# STM.net
KiCad netlist of a schematic drawn in Altium Designer
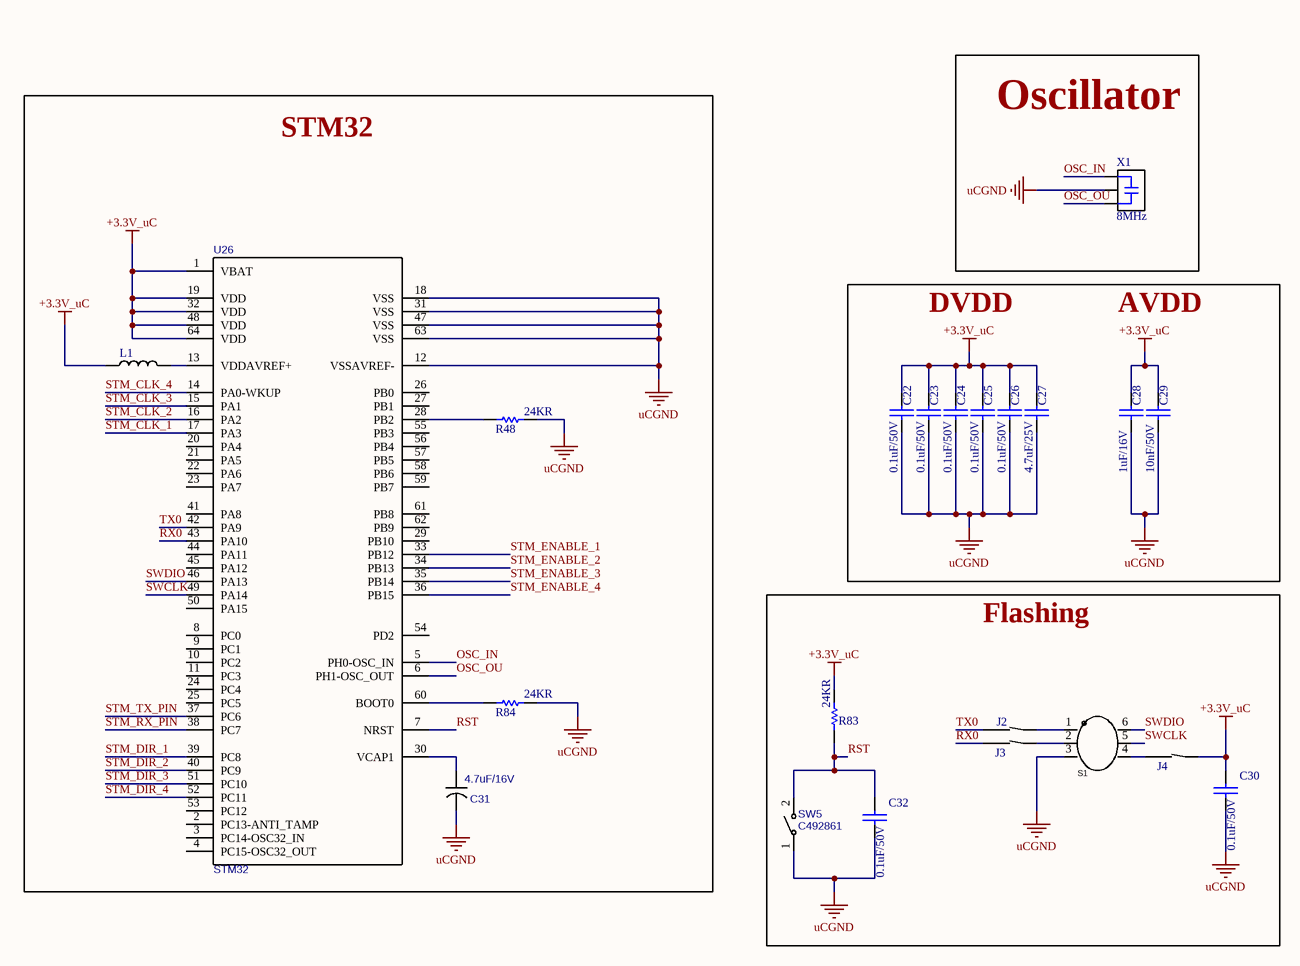
[diagram p0: STM.SchDoc]

(export (version "E")
  (design (tool "Eeschema 10.0.6"))
  (components
    (comp (ref "C22")
      (value "0.1uF/50V")
      (footprint "PCBComponent_1")
      (description "C1591")
      (fields (field (name "CREATED BY") "NourAldin"))
      (libsource (lib "0603 Capacitor") (part "0603 Capacitor"))
    )
    (comp (ref "C23")
      (value "0.1uF/50V")
      (footprint "PCBComponent_1")
      (description "C1591")
      (fields (field (name "CREATED BY") "NourAldin"))
      (libsource (lib "0603 Capacitor") (part "0603 Capacitor"))
    )
    (comp (ref "C24")
      (value "0.1uF/50V")
      (footprint "PCBComponent_1")
      (description "C1591")
      (fields (field (name "CREATED BY") "NourAldin"))
      (libsource (lib "0603 Capacitor") (part "0603 Capacitor"))
    )
    (comp (ref "C25")
      (value "0.1uF/50V")
      (footprint "PCBComponent_1")
      (description "C1591")
      (fields (field (name "CREATED BY") "NourAldin"))
      (libsource (lib "0603 Capacitor") (part "0603 Capacitor"))
    )
    (comp (ref "C26")
      (value "0.1uF/50V")
      (footprint "PCBComponent_1")
      (description "C1591")
      (fields (field (name "CREATED BY") "NourAldin"))
      (libsource (lib "0603 Capacitor") (part "0603 Capacitor"))
    )
    (comp (ref "C27")
      (value "4.7uF/25V")
      (footprint "PCBComponent_1")
      (description "C69335")
      (fields (field (name "CREATED BY") "NourAldin"))
      (libsource (lib "0603 Capacitor") (part "0603 Capacitor"))
    )
    (comp (ref "C28")
      (value "1uF/16V")
      (footprint "PCBComponent_1")
      (description "C1592")
      (fields (field (name "CREATED BY") "NourAldin"))
      (libsource (lib "0603 Capacitor") (part "0603 Capacitor"))
    )
    (comp (ref "C29")
      (value "10nF/50V")
      (footprint "PCBComponent_1")
      (description "C100042")
      (fields (field (name "CREATED BY") "NourAldin"))
      (libsource (lib "0603 Capacitor") (part "0603 Capacitor"))
    )
    (comp (ref "C30")
      (value "0.1uF/50V")
      (footprint "PCBComponent_1")
      (description "C1591")
      (fields (field (name "CREATED BY") "NourAldin"))
      (libsource (lib "0603 Capacitor") (part "0603 Capacitor"))
    )
    (comp (ref "C31")
      (value "4.7uF/16V")
      (footprint "CASE-B_3528")
      (description "C7206")
      (fields
        (field (name "MANUFACTURER") "Kyocera AVX")
        (field (name "MANUFACTURER PART") "TAJR106K006RNJ")
        (field (name "CONTRIBUTOR") "LCSC")
      )
      (libsource (lib "DIVERSE") (part "3528  Tantalum Cap"))
    )
    (comp (ref "C32")
      (value "0.1uF/50V")
      (footprint "PCBComponent_1")
      (description "C1591")
      (fields (field (name "CREATED BY") "NourAldin"))
      (libsource (lib "0603 Capacitor") (part "0603 Capacitor"))
    )
    (comp (ref "J2") (value "Jumper") (footprint "Jumper") (libsource (lib "DIVERSE") (part "Jumper")))
    (comp (ref "J3") (value "Jumper") (footprint "Jumper") (libsource (lib "DIVERSE") (part "Jumper")))
    (comp (ref "J4") (value "Jumper") (footprint "Jumper") (libsource (lib "DIVERSE") (part "Jumper")))
    (comp (ref "L1")
      (value "CMI201209X100KT")
      (footprint "INDC2012X06N")
      (description "C99366")
      (fields (field (name "CREATED BY") "NourAldin"))
      (libsource (lib "0805 Inductor") (part "0805 SMD INDUCTOR"))
    )
    (comp (ref "R48")
      (value "24KR")
      (footprint "RESC1608X06N")
      (description "C2930081")
      (fields (field (name "CREATED BY") "NourAldin"))
      (libsource (lib "0603 Resistor") (part "0603 Resistor"))
    )
    (comp (ref "R83")
      (value "24KR")
      (footprint "RESC1608X06N")
      (description "C2930081")
      (fields (field (name "CREATED BY") "NourAldin"))
      (libsource (lib "0603 Resistor") (part "0603 Resistor"))
    )
    (comp (ref "R84")
      (value "24KR")
      (footprint "RESC1608X06N")
      (description "C2930081")
      (fields (field (name "CREATED BY") "NourAldin"))
      (libsource (lib "0603 Resistor") (part "0603 Resistor"))
    )
    (comp (ref "S1")
      (value "STM Debug")
      (footprint "STM_Debug")
      (description "Wurth Elektronik 490107670612")
      (fields
        (field (name "MANUFACTURER") "XKB Connection(中国星坤)")
        (field (name "MANUFACTURER PART") "X4621WVS-2x03I-C40D64")
      )
      (libsource (lib "DIVERSE") (part "STM Debug"))
    )
    (comp (ref "SW5")
      (value "C492861")
      (footprint "SW-SMD_L4.0-W3.0-LS4.8")
      (fields
        (field (name "MANUFACTURER") "Yuandi(元迪)")
        (field (name "MANUFACTURER PART") "TS-1071AS-A1B3-D4")
        (field (name "CONTRIBUTOR") "LCSC")
      )
      (libsource (lib "DIVERSE") (part "tact switch"))
    )
    (comp (ref "U26")
      (value "STM32")
      (footprint "LQFP-64_L10.0-W10.0-P0.50-LS12.0-BL")
      (description "C74524")
      (fields (field (name "MANUFACTURER") "ST(意法半导体)") (field (name "MANUFACTURER PART") "STM32F401RCT6"))
      (libsource (lib "DIVERSE") (part "STM32F401RCT6"))
    )
    (comp (ref "X1")
      (value "8MHz")
      (footprint "SMD3213-3P")
      (description "C907975")
      (fields
        (field (name "MANUFACTURER") "Murata")
        (field (name "MANUFACTURER PART NUMBER") "CSTCE16M0V53-R0")
      )
      (libsource (lib "CO2_Lib") (part "CSTCE16M0V53-R0"))
    )
  )
  (nets
    (net (code "1") (name "+3.3V_uC") (class "Default")
      (node (ref "C22") (pin "2") (pinfunction "2_2") (pintype "passive"))
      (node (ref "C23") (pin "2") (pinfunction "2_2") (pintype "passive"))
      (node (ref "C24") (pin "2") (pinfunction "2_2") (pintype "passive"))
      (node (ref "C25") (pin "2") (pinfunction "2_2") (pintype "passive"))
      (node (ref "C26") (pin "2") (pinfunction "2_2") (pintype "passive"))
      (node (ref "C27") (pin "2") (pinfunction "2_2") (pintype "passive"))
      (node (ref "C28") (pin "2") (pinfunction "2_2") (pintype "passive"))
      (node (ref "C29") (pin "2") (pinfunction "2_2") (pintype "passive"))
      (node (ref "C30") (pin "2") (pinfunction "2_2") (pintype "passive"))
      (node (ref "J4") (pin "2") (pinfunction "2_2") (pintype "passive"))
      (node (ref "L1") (pin "1") (pinfunction "1_1") (pintype "passive"))
      (node (ref "R83") (pin "1") (pinfunction "1_1") (pintype "passive"))
      (node (ref "U26") (pin "1") (pinfunction "VBAT_1") (pintype "passive"))
      (node (ref "U26") (pin "19") (pinfunction "VDD_19") (pintype "passive"))
      (node (ref "U26") (pin "32") (pinfunction "VDD_32") (pintype "passive"))
      (node (ref "U26") (pin "48") (pinfunction "VDD_48") (pintype "passive"))
      (node (ref "U26") (pin "64") (pinfunction "VDD_64") (pintype "passive"))
    )
    (net (code "2") (name "/OSC_IN") (class "Default")
      (node (ref "U26") (pin "5") (pinfunction "PH0-OSC_IN_5") (pintype "passive"))
      (node (ref "X1") (pin "1") (pinfunction "1_1") (pintype "passive"))
    )
    (net (code "3") (name "/OSC_OU") (class "Default")
      (node (ref "U26") (pin "6") (pinfunction "PH1-OSC_OUT_6") (pintype "passive"))
      (node (ref "X1") (pin "3") (pinfunction "3_3") (pintype "passive"))
    )
    (net (code "4") (name "/RST") (class "Default")
      (node (ref "C32") (pin "2") (pinfunction "2_2") (pintype "passive"))
      (node (ref "R83") (pin "2") (pinfunction "2_2") (pintype "passive"))
      (node (ref "SW5") (pin "2") (pinfunction "2_2") (pintype "passive"))
      (node (ref "U26") (pin "7") (pinfunction "NRST_7") (pintype "passive"))
    )
    (net (code "5") (name "/RX0") (class "Default")
      (node (ref "J3") (pin "1") (pinfunction "1_1") (pintype "passive"))
      (node (ref "U26") (pin "43") (pinfunction "PA10_43") (pintype "passive"))
    )
    (net (code "6") (name "/STM_CLK_1") (class "Default")
      (node (ref "U26") (pin "17") (pinfunction "PA3_17") (pintype "passive"))
    )
    (net (code "7") (name "/STM_CLK_2") (class "Default")
      (node (ref "U26") (pin "16") (pinfunction "PA2_16") (pintype "passive"))
    )
    (net (code "8") (name "/STM_CLK_3") (class "Default")
      (node (ref "U26") (pin "15") (pinfunction "PA1_15") (pintype "passive"))
    )
    (net (code "9") (name "/STM_CLK_4") (class "Default")
      (node (ref "U26") (pin "14") (pinfunction "PA0-WKUP_14") (pintype "passive"))
    )
    (net (code "10") (name "/STM_DIR_1") (class "Default")
      (node (ref "U26") (pin "39") (pinfunction "PC8_39") (pintype "passive"))
    )
    (net (code "11") (name "/STM_DIR_2") (class "Default")
      (node (ref "U26") (pin "40") (pinfunction "PC9_40") (pintype "passive"))
    )
    (net (code "12") (name "/STM_DIR_3") (class "Default")
      (node (ref "U26") (pin "51") (pinfunction "PC10_51") (pintype "passive"))
    )
    (net (code "13") (name "/STM_DIR_4") (class "Default")
      (node (ref "U26") (pin "52") (pinfunction "PC11_52") (pintype "passive"))
    )
    (net (code "14") (name "/STM_ENABLE_1") (class "Default")
      (node (ref "U26") (pin "33") (pinfunction "PB12_33") (pintype "passive"))
    )
    (net (code "15") (name "/STM_ENABLE_2") (class "Default")
      (node (ref "U26") (pin "34") (pinfunction "PB13_34") (pintype "passive"))
    )
    (net (code "16") (name "/STM_ENABLE_3") (class "Default")
      (node (ref "U26") (pin "35") (pinfunction "PB14_35") (pintype "passive"))
    )
    (net (code "17") (name "/STM_ENABLE_4") (class "Default")
      (node (ref "U26") (pin "36") (pinfunction "PB15_36") (pintype "passive"))
    )
    (net (code "18") (name "/STM_RX_PIN") (class "Default")
      (node (ref "U26") (pin "38") (pinfunction "PC7_38") (pintype "passive"))
    )
    (net (code "19") (name "/STM_TX_PIN") (class "Default")
      (node (ref "U26") (pin "37") (pinfunction "PC6_37") (pintype "passive"))
    )
    (net (code "20") (name "/SWCLK") (class "Default")
      (node (ref "S1") (pin "5") (pinfunction "5_5") (pintype "passive"))
      (node (ref "U26") (pin "49") (pinfunction "PA14_49") (pintype "passive"))
    )
    (net (code "21") (name "/SWDIO") (class "Default")
      (node (ref "S1") (pin "6") (pinfunction "6_6") (pintype "passive"))
      (node (ref "U26") (pin "46") (pinfunction "PA13_46") (pintype "passive"))
    )
    (net (code "22") (name "/TX0") (class "Default")
      (node (ref "J2") (pin "1") (pinfunction "1_1") (pintype "passive"))
      (node (ref "U26") (pin "42") (pinfunction "PA9_42") (pintype "passive"))
    )
    (net (code "23") (name "Net-(J2-Pad2)") (class "Default")
      (node (ref "J2") (pin "2") (pinfunction "2_2") (pintype "passive"))
      (node (ref "S1") (pin "1") (pinfunction "1_1") (pintype "passive"))
    )
    (net (code "24") (name "Net-(J3-Pad2)") (class "Default")
      (node (ref "J3") (pin "2") (pinfunction "2_2") (pintype "passive"))
      (node (ref "S1") (pin "2") (pinfunction "2_2") (pintype "passive"))
    )
    (net (code "25") (name "Net-(J4-Pad1)") (class "Default")
      (node (ref "J4") (pin "1") (pinfunction "1_1") (pintype "passive"))
      (node (ref "S1") (pin "4") (pinfunction "4_4") (pintype "passive"))
    )
    (net (code "26") (name "Net-(U26-BOOT0)") (class "Default")
      (node (ref "R84") (pin "2") (pinfunction "2_2") (pintype "passive"))
      (node (ref "U26") (pin "60") (pinfunction "BOOT0_60") (pintype "passive"))
    )
    (net (code "27") (name "Net-(U26-PB2)") (class "Default")
      (node (ref "R48") (pin "2") (pinfunction "2_2") (pintype "passive"))
      (node (ref "U26") (pin "28") (pinfunction "PB2_28") (pintype "passive"))
    )
    (net (code "28") (name "Net-(U26-VCAP1)") (class "Default")
      (node (ref "C31") (pin "1") (pinfunction "1_1") (pintype "passive"))
      (node (ref "U26") (pin "30") (pinfunction "VCAP1_30") (pintype "passive"))
    )
    (net (code "29") (name "Net-(U26-VDDAVREF+)") (class "Default")
      (node (ref "L1") (pin "2") (pinfunction "2_2") (pintype "passive"))
      (node (ref "U26") (pin "13") (pinfunction "VDDAVREF+_13") (pintype "passive"))
    )
    (net (code "30") (name "uCGND") (class "Default")
      (node (ref "C22") (pin "1") (pinfunction "1_1") (pintype "passive"))
      (node (ref "C23") (pin "1") (pinfunction "1_1") (pintype "passive"))
      (node (ref "C24") (pin "1") (pinfunction "1_1") (pintype "passive"))
      (node (ref "C25") (pin "1") (pinfunction "1_1") (pintype "passive"))
      (node (ref "C26") (pin "1") (pinfunction "1_1") (pintype "passive"))
      (node (ref "C27") (pin "1") (pinfunction "1_1") (pintype "passive"))
      (node (ref "C28") (pin "1") (pinfunction "1_1") (pintype "passive"))
      (node (ref "C29") (pin "1") (pinfunction "1_1") (pintype "passive"))
      (node (ref "C30") (pin "1") (pinfunction "1_1") (pintype "passive"))
      (node (ref "C31") (pin "2") (pinfunction "2_2") (pintype "passive"))
      (node (ref "C32") (pin "1") (pinfunction "1_1") (pintype "passive"))
      (node (ref "R48") (pin "1") (pinfunction "1_1") (pintype "passive"))
      (node (ref "R84") (pin "1") (pinfunction "1_1") (pintype "passive"))
      (node (ref "S1") (pin "3") (pinfunction "3_3") (pintype "passive"))
      (node (ref "SW5") (pin "1") (pinfunction "1_1") (pintype "passive"))
      (node (ref "U26") (pin "12") (pinfunction "VSSAVREF-_12") (pintype "passive"))
      (node (ref "U26") (pin "18") (pinfunction "VSS_18") (pintype "passive"))
      (node (ref "U26") (pin "31") (pinfunction "VSS_31") (pintype "passive"))
      (node (ref "U26") (pin "47") (pinfunction "VSS_47") (pintype "passive"))
      (node (ref "U26") (pin "63") (pinfunction "VSS_63") (pintype "passive"))
      (node (ref "X1") (pin "2") (pinfunction "2_2") (pintype "passive"))
    )
    (net (code "31") (name "unconnected-(U26-PA4-Pad20)") (class "Default")
      (node (ref "U26") (pin "20") (pinfunction "PA4_20") (pintype "passive"))
    )
    (net (code "32") (name "unconnected-(U26-PA5-Pad21)") (class "Default")
      (node (ref "U26") (pin "21") (pinfunction "PA5_21") (pintype "passive"))
    )
    (net (code "33") (name "unconnected-(U26-PA6-Pad22)") (class "Default")
      (node (ref "U26") (pin "22") (pinfunction "PA6_22") (pintype "passive"))
    )
    (net (code "34") (name "unconnected-(U26-PA7-Pad23)") (class "Default")
      (node (ref "U26") (pin "23") (pinfunction "PA7_23") (pintype "passive"))
    )
    (net (code "35") (name "unconnected-(U26-PA8-Pad41)") (class "Default")
      (node (ref "U26") (pin "41") (pinfunction "PA8_41") (pintype "passive"))
    )
    (net (code "36") (name "unconnected-(U26-PA11-Pad44)") (class "Default")
      (node (ref "U26") (pin "44") (pinfunction "PA11_44") (pintype "passive"))
    )
    (net (code "37") (name "unconnected-(U26-PA12-Pad45)") (class "Default")
      (node (ref "U26") (pin "45") (pinfunction "PA12_45") (pintype "passive"))
    )
    (net (code "38") (name "unconnected-(U26-PA15-Pad50)") (class "Default")
      (node (ref "U26") (pin "50") (pinfunction "PA15_50") (pintype "passive"))
    )
    (net (code "39") (name "unconnected-(U26-PB0-Pad26)") (class "Default")
      (node (ref "U26") (pin "26") (pinfunction "PB0_26") (pintype "passive"))
    )
    (net (code "40") (name "unconnected-(U26-PB1-Pad27)") (class "Default")
      (node (ref "U26") (pin "27") (pinfunction "PB1_27") (pintype "passive"))
    )
    (net (code "41") (name "unconnected-(U26-PB3-Pad55)") (class "Default")
      (node (ref "U26") (pin "55") (pinfunction "PB3_55") (pintype "passive"))
    )
    (net (code "42") (name "unconnected-(U26-PB4-Pad56)") (class "Default")
      (node (ref "U26") (pin "56") (pinfunction "PB4_56") (pintype "passive"))
    )
    (net (code "43") (name "unconnected-(U26-PB5-Pad57)") (class "Default")
      (node (ref "U26") (pin "57") (pinfunction "PB5_57") (pintype "passive"))
    )
    (net (code "44") (name "unconnected-(U26-PB6-Pad58)") (class "Default")
      (node (ref "U26") (pin "58") (pinfunction "PB6_58") (pintype "passive"))
    )
    (net (code "45") (name "unconnected-(U26-PB7-Pad59)") (class "Default")
      (node (ref "U26") (pin "59") (pinfunction "PB7_59") (pintype "passive"))
    )
    (net (code "46") (name "unconnected-(U26-PB8-Pad61)") (class "Default")
      (node (ref "U26") (pin "61") (pinfunction "PB8_61") (pintype "passive"))
    )
    (net (code "47") (name "unconnected-(U26-PB9-Pad62)") (class "Default")
      (node (ref "U26") (pin "62") (pinfunction "PB9_62") (pintype "passive"))
    )
    (net (code "48") (name "unconnected-(U26-PB10-Pad29)") (class "Default")
      (node (ref "U26") (pin "29") (pinfunction "PB10_29") (pintype "passive"))
    )
    (net (code "49") (name "unconnected-(U26-PC0-Pad8)") (class "Default")
      (node (ref "U26") (pin "8") (pinfunction "PC0_8") (pintype "passive"))
    )
    (net (code "50") (name "unconnected-(U26-PC1-Pad9)") (class "Default")
      (node (ref "U26") (pin "9") (pinfunction "PC1_9") (pintype "passive"))
    )
    (net (code "51") (name "unconnected-(U26-PC2-Pad10)") (class "Default")
      (node (ref "U26") (pin "10") (pinfunction "PC2_10") (pintype "passive"))
    )
    (net (code "52") (name "unconnected-(U26-PC3-Pad11)") (class "Default")
      (node (ref "U26") (pin "11") (pinfunction "PC3_11") (pintype "passive"))
    )
    (net (code "53") (name "unconnected-(U26-PC4-Pad24)") (class "Default")
      (node (ref "U26") (pin "24") (pinfunction "PC4_24") (pintype "passive"))
    )
    (net (code "54") (name "unconnected-(U26-PC5-Pad25)") (class "Default")
      (node (ref "U26") (pin "25") (pinfunction "PC5_25") (pintype "passive"))
    )
    (net (code "55") (name "unconnected-(U26-PC12-Pad53)") (class "Default")
      (node (ref "U26") (pin "53") (pinfunction "PC12_53") (pintype "passive"))
    )
    (net (code "56") (name "unconnected-(U26-PC13-ANTI_TAMP-Pad2)") (class "Default")
      (node (ref "U26") (pin "2") (pinfunction "PC13-ANTI_TAMP_2") (pintype "passive"))
    )
    (net (code "57") (name "unconnected-(U26-PC14-OSC32_IN-Pad3)") (class "Default")
      (node (ref "U26") (pin "3") (pinfunction "PC14-OSC32_IN_3") (pintype "passive"))
    )
    (net (code "58") (name "unconnected-(U26-PC15-OSC32_OUT-Pad4)") (class "Default")
      (node (ref "U26") (pin "4") (pinfunction "PC15-OSC32_OUT_4") (pintype "passive"))
    )
    (net (code "59") (name "unconnected-(U26-PD2-Pad54)") (class "Default")
      (node (ref "U26") (pin "54") (pinfunction "PD2_54") (pintype "passive"))
    )
  )
)
